# RS-485.net
KiCad netlist of a schematic drawn in Altium Designer
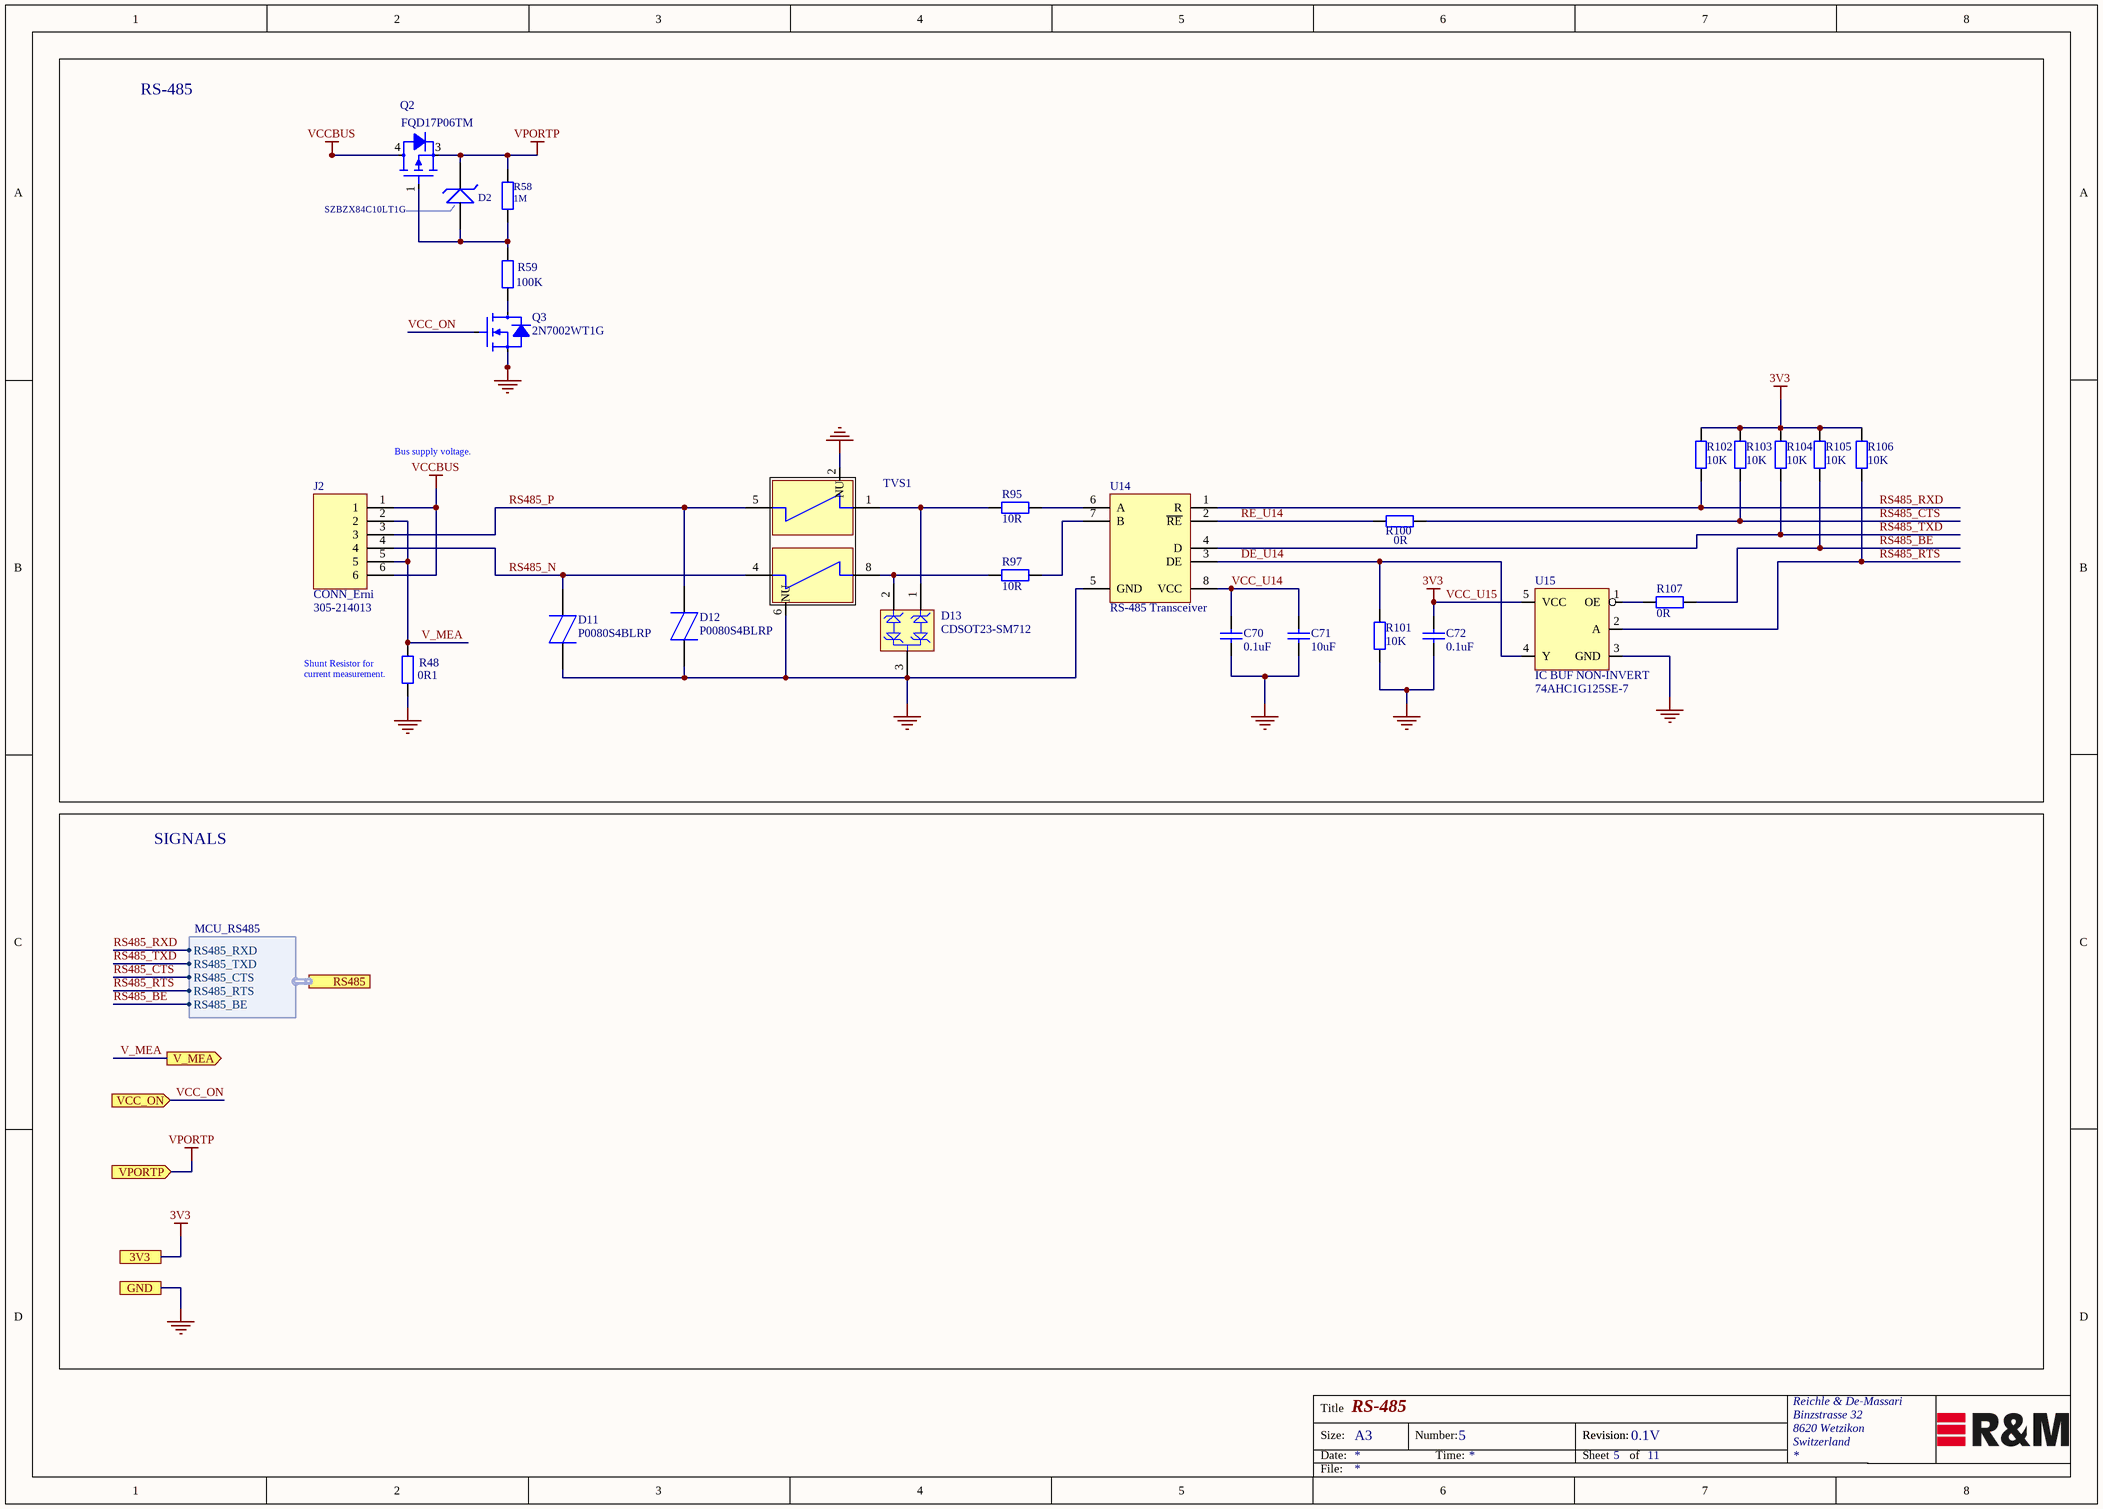
[diagram p0: RS-485.SchDoc]

(export (version "E")
  (design (tool "Eeschema 10.0.6"))
  (components
    (comp (ref "C70")
      (value "0.1uF")
      (footprint "Ceramic Capacitor 0402 EIA")
      (description "0.1µF ±20% 10V Ceramic Capacitor X5R 0402 (1005 Metric)")
      (fields (field (name "TOLERANCE") "20%") (field (name "VOLTAGE") "10VDC"))
      (libsource (lib "RDM_ALT_SCH") (part "Cap_0.1uF_0402_10V"))
    )
    (comp (ref "C71")
      (value "10uF")
      (footprint "Ceramic Capacitor 0402 EIA")
      (description "10µF ±20% 10V Ceramic Capacitor X5R 0402 (1005 Metric)")
      (fields (field (name "TOLERANCE") "20%") (field (name "VOLTAGE") "10VDC"))
      (libsource (lib "RDM_ALT_SCH") (part "Cap_10uF_0402_10V"))
    )
    (comp (ref "C72")
      (value "0.1uF")
      (footprint "Ceramic Capacitor 0402 EIA")
      (description "0.1µF ±20% 10V Ceramic Capacitor X5R 0402 (1005 Metric)")
      (fields (field (name "TOLERANCE") "20%") (field (name "VOLTAGE") "10VDC"))
      (libsource (lib "RDM_ALT_SCH") (part "Cap_0.1uF_0402_10V"))
    )
    (comp (ref "D2")
      (value "SZBZX84C10LT1G")
      (footprint "SOT-23_BZX84")
      (description "Zener Diode 10V 225mW ±6% Oberflächenmontage SOT-23-3 (TO-236)")
      (fields (field (name "MANUFACTURER") "ON Semiconductor") (field (name "POWER") "225mW"))
      (libsource (lib "RDM_ALT_SCH") (part "Diode_SZBZX84C10LT1G"))
    )
    (comp (ref "D11")
      (value "P0080S4BLRP")
      (footprint "P0080S4BLRP")
      (fields (field (name "MANUFACTURER") "Littelfuse") (field (name "MANUFACTURER PARTNR") "P0080S4BLRP"))
      (libsource (lib "RDM_ALT_SCH") (part "P0080S4BLRP"))
    )
    (comp (ref "D12")
      (value "P0080S4BLRP")
      (footprint "P0080S4BLRP")
      (fields (field (name "MANUFACTURER") "Littelfuse") (field (name "MANUFACTURER PARTNR") "P0080S4BLRP"))
      (libsource (lib "RDM_ALT_SCH") (part "P0080S4BLRP"))
    )
    (comp (ref "D13")
      (value "CDSOT23-SM712")
      (footprint "BOUR-SOT23-3_V")
      (description "TVSDiode, 26V, 14V Clamp 17A (8/20µs) Ipp, Surface Mount SOT-23-3, Applications RS-485")
      (fields (field (name "MANUFACTURER") "Bourns") (field (name "VOLTAGE") "26V, 14V"))
      (libsource (lib "RDM_ALT_SCH") (part "Diode_TVS_26V"))
    )
    (comp (ref "J2")
      (value "CONN_Erni")
      (footprint "ERNI_214013 Randmontage_6_R")
      (description "Headers & Wire Housings 6P 1.27MM SNGL ROW R/A MALE BLK")
      (fields (field (name "MANUFACTURER") "ERNI") (field (name "SUPPLIER PART NUMBER 1") "305-214013"))
      (libsource (lib "RDM_ALT_SCH") (part "CONN_Erni_6_214013"))
    )
    (comp (ref "Q2")
      (value "FQD17P06TM")
      (footprint "DPAK_FQU17P06")
      (description "P-Channel 60V 12A (Tc) 2.5W (Ta), 44W (Tc) Surface Mount D-Pak")
      (fields (field (name "TOLERANCE") "NA") (field (name "VOLTAGE") "60V"))
      (libsource (lib "RDM_ALT_SCH") (part "FQD17P06TM"))
    )
    (comp (ref "Q3")
      (value "2N7002WT1G")
      (footprint "SOT323_2N7002WT1G")
      (description "N-Channel 60V 310mA (Ta) 280mW (Tj) Surface Mount SC-70-3 (SOT323)")
      (fields (field (name "TOLERANCE") "NA") (field (name "VOLTAGE") "60V"))
      (libsource (lib "RDM_ALT_SCH") (part "2N7002WT1G"))
    )
    (comp (ref "R48")
      (value "0R1")
      (footprint "Resistor 4527")
      (fields
        (field (name "TOLERANCE") "±1%")
        (field (name "POWER") "5W")
        (field (name "MANUFACTURER") "Vishay / Dale")
      )
      (libsource (lib "RDM_ALT_SCH") (part "Res_0R1"))
    )
    (comp (ref "R58")
      (value "1M")
      (footprint "Resistor 0402 EIA")
      (description "1 MOhms ±1% 0.1W, 1/10W Chip Resistor 0402 (1005 Metric) Anti-Sulfur Thin Film")
      (fields (field (name "MANUFACTURER") "Vishay Beyschlag") (field (name "POWER") "0.1W, 1/10W"))
      (libsource (lib "RDM_ALT_SCH") (part "Res_1M_0402"))
    )
    (comp (ref "R59")
      (value "100K")
      (footprint "Resistor 0402 EIA")
      (description "100 kOhms ±0,1% 0,063W, 1/16W Chip-Widerstand 0402 (1005 metrisch) Dünnschicht")
      (fields (field (name "TOLERANCE") "±0.1%") (field (name "POWER") "0,063W, 1/16W"))
      (libsource (lib "RDM_ALT_SCH") (part "Res_100K_0402"))
    )
    (comp (ref "R95")
      (value "10R")
      (footprint "Resistor 0603 EIA")
      (description "SMD 1/4watt 10ohms 1%")
      (fields (field (name "TOLERANCE") "1%") (field (name "POWER") "250mW"))
      (libsource (lib "RDM_ALT_SCH") (part "Res_10R_0603"))
    )
    (comp (ref "R97")
      (value "10R")
      (footprint "Resistor 0603 EIA")
      (description "SMD 1/4watt 10ohms 1%")
      (fields (field (name "TOLERANCE") "1%") (field (name "POWER") "250mW"))
      (libsource (lib "RDM_ALT_SCH") (part "Res_10R_0603"))
    )
    (comp (ref "R100")
      (value "0R")
      (footprint "Resistor 0402 EIA")
      (description "0 Ohms Resistor 0402")
      (fields (field (name "POWER") "100mW") (field (name "MANUFACTURER") "Panasonic Electronic Components"))
      (libsource (lib "RDM_ALT_SCH") (part "Res_0R_0402"))
    )
    (comp (ref "R101")
      (value "10K")
      (footprint "Resistor 0402 EIA")
      (description "SMD 10K ohm 1% 50V General Purpose")
      (fields (field (name "TOLERANCE") "1%") (field (name "POWER") "63mW"))
      (libsource (lib "RDM_ALT_SCH") (part "Res_10K_0402"))
    )
    (comp (ref "R102")
      (value "10K")
      (footprint "Resistor 0402 EIA")
      (description "SMD 10K ohm 1% 50V General Purpose")
      (fields (field (name "TOLERANCE") "1%") (field (name "POWER") "63mW"))
      (libsource (lib "RDM_ALT_SCH") (part "Res_10K_0402"))
    )
    (comp (ref "R103")
      (value "10K")
      (footprint "Resistor 0402 EIA")
      (description "SMD 10K ohm 1% 50V General Purpose")
      (fields (field (name "TOLERANCE") "1%") (field (name "POWER") "63mW"))
      (libsource (lib "RDM_ALT_SCH") (part "Res_10K_0402"))
    )
    (comp (ref "R104")
      (value "10K")
      (footprint "Resistor 0402 EIA")
      (description "SMD 10K ohm 1% 50V General Purpose")
      (fields (field (name "TOLERANCE") "1%") (field (name "POWER") "63mW"))
      (libsource (lib "RDM_ALT_SCH") (part "Res_10K_0402"))
    )
    (comp (ref "R105")
      (value "10K")
      (footprint "Resistor 0402 EIA")
      (description "SMD 10K ohm 1% 50V General Purpose")
      (fields (field (name "TOLERANCE") "1%") (field (name "POWER") "63mW"))
      (libsource (lib "RDM_ALT_SCH") (part "Res_10K_0402"))
    )
    (comp (ref "R106")
      (value "10K")
      (footprint "Resistor 0402 EIA")
      (description "SMD 10K ohm 1% 50V General Purpose")
      (fields (field (name "TOLERANCE") "1%") (field (name "POWER") "63mW"))
      (libsource (lib "RDM_ALT_SCH") (part "Res_10K_0402"))
    )
    (comp (ref "R107")
      (value "0R")
      (footprint "Resistor 0402 EIA")
      (description "0 Ohms Resistor 0402")
      (fields (field (name "POWER") "100mW") (field (name "MANUFACTURER") "Panasonic Electronic Components"))
      (libsource (lib "RDM_ALT_SCH") (part "Res_0R_0402"))
    )
    (comp (ref "TVS1")
      (value "TBU-CA065-200-WH")
      (footprint "Bourns_TBU_PL060_WH")
      (description "TBU-PL Series dual 50 ohm Surge Suppressors, bi-directional")
      (fields (field (name "MANUFACTURER") "Bourns") (field (name "VOLTAGE") "350V"))
      (libsource (lib "RDM_ALT_SCH") (part "Bourns_TBU-PL060-200-WH"))
    )
    (comp (ref "U14")
      (value "RS-485 Transceiver")
      (footprint "TI_D (R-PDSO-G8)_8_R")
      (description "RS-485 Interface IC 3.3V Differential Transceivers")
      (fields (field (name "MANUFACTURER") "Texas Instruments"))
      (libsource (lib "RDM_ALT_SCH") (part "SN65HVD11DR"))
    )
    (comp (ref "U15")
      (value "IC BUF NON-INVERT")
      (footprint "SOT353")
      (description "Buffer, Non-Inverting 1 Element 1 Bit per Element 3-State Output SOT-353")
      (fields
        (field (name "MANUFACTURER") "Diodes Incorporated")
        (field (name "MANUFACTURER PARTNR") "74AHC1G125SE-7")
      )
      (libsource (lib "RDM_ALT_SCH") (part "74AHC1G125SE-7"))
    )
  )
  (nets
    (net (code "2") (name "/DE_U14") (class "Default")
      (node (ref "R101") (pin "1") (pinfunction "1_1") (pintype "passive"))
      (node (ref "U14") (pin "3") (pinfunction "DE_3") (pintype "passive"))
      (node (ref "U15") (pin "4") (pinfunction "Y_4") (pintype "passive"))
    )
    (net (code "3") (name "/RE_U14") (class "Default")
      (node (ref "R100") (pin "1") (pinfunction "1_1") (pintype "passive"))
      (node (ref "U14") (pin "2") (pinfunction "~{RE}_2") (pintype "passive"))
    )
    (net (code "4") (name "/RS485_BE") (class "Default")
      (node (ref "R105") (pin "2") (pinfunction "2_2") (pintype "passive"))
      (node (ref "R107") (pin "2") (pinfunction "2_2") (pintype "passive"))
    )
    (net (code "5") (name "/RS485_CTS") (class "Default")
      (node (ref "R100") (pin "2") (pinfunction "2_2") (pintype "passive"))
      (node (ref "R103") (pin "2") (pinfunction "2_2") (pintype "passive"))
    )
    (net (code "6") (name "/RS485_N") (class "Default")
      (node (ref "D11") (pin "2") (pinfunction "K_2") (pintype "passive"))
      (node (ref "J2") (pin "4") (pinfunction "4_4") (pintype "passive"))
      (node (ref "TVS1") (pin "4") (pinfunction "4_4") (pintype "passive"))
    )
    (net (code "7") (name "/RS485_P") (class "Default")
      (node (ref "D12") (pin "2") (pinfunction "K_2") (pintype "passive"))
      (node (ref "J2") (pin "3") (pinfunction "3_3") (pintype "passive"))
      (node (ref "TVS1") (pin "5") (pinfunction "5_5") (pintype "passive"))
    )
    (net (code "8") (name "/RS485_RTS") (class "Default")
      (node (ref "R106") (pin "2") (pinfunction "2_2") (pintype "passive"))
      (node (ref "U15") (pin "2") (pinfunction "A_2") (pintype "passive"))
    )
    (net (code "9") (name "/RS485_RXD") (class "Default")
      (node (ref "R102") (pin "2") (pinfunction "2_2") (pintype "passive"))
      (node (ref "U14") (pin "1") (pinfunction "R_1") (pintype "tri_state"))
    )
    (net (code "10") (name "/RS485_TXD") (class "Default")
      (node (ref "R104") (pin "2") (pinfunction "2_2") (pintype "passive"))
      (node (ref "U14") (pin "4") (pinfunction "D_4") (pintype "passive"))
    )
    (net (code "11") (name "/VCC_ON") (class "Default")
      (node (ref "Q3") (pin "1") (pinfunction "1_1") (pintype "passive"))
    )
    (net (code "12") (name "/VCC_U14") (class "Default")
      (node (ref "C70") (pin "2") (pinfunction "2_2") (pintype "passive"))
      (node (ref "C71") (pin "2") (pinfunction "2_2") (pintype "passive"))
      (node (ref "U14") (pin "8") (pinfunction "VCC_8") (pintype "power_in"))
    )
    (net (code "13") (name "/V_MEA") (class "Default")
      (node (ref "J2") (pin "2") (pinfunction "2_2") (pintype "passive"))
      (node (ref "J2") (pin "5") (pinfunction "5_5") (pintype "passive"))
      (node (ref "R48") (pin "1") (pinfunction "1_1") (pintype "passive"))
    )
    (net (code "15") (name "3V3") (class "Default")
      (node (ref "C72") (pin "2") (pinfunction "2_2") (pintype "passive"))
      (node (ref "R102") (pin "1") (pinfunction "1_1") (pintype "passive"))
      (node (ref "R103") (pin "1") (pinfunction "1_1") (pintype "passive"))
      (node (ref "R104") (pin "1") (pinfunction "1_1") (pintype "passive"))
      (node (ref "R105") (pin "1") (pinfunction "1_1") (pintype "passive"))
      (node (ref "R106") (pin "1") (pinfunction "1_1") (pintype "passive"))
      (node (ref "U15") (pin "5") (pinfunction "VCC_5") (pintype "passive"))
    )
    (net (code "16") (name "GND") (class "Default")
      (node (ref "C70") (pin "1") (pinfunction "1_1") (pintype "passive"))
      (node (ref "C71") (pin "1") (pinfunction "1_1") (pintype "passive"))
      (node (ref "C72") (pin "1") (pinfunction "1_1") (pintype "passive"))
      (node (ref "D11") (pin "1") (pinfunction "A_1") (pintype "passive"))
      (node (ref "D12") (pin "1") (pinfunction "A_1") (pintype "passive"))
      (node (ref "D13") (pin "3") (pinfunction "3_3") (pintype "passive"))
      (node (ref "Q3") (pin "2") (pinfunction "2_2") (pintype "passive"))
      (node (ref "R101") (pin "2") (pinfunction "2_2") (pintype "passive"))
      (node (ref "R48") (pin "2") (pinfunction "2_2") (pintype "passive"))
      (node (ref "TVS1") (pin "2") (pinfunction "NU_2") (pintype "passive"))
      (node (ref "TVS1") (pin "6") (pinfunction "NU_6") (pintype "passive"))
      (node (ref "U14") (pin "5") (pinfunction "GND_5") (pintype "passive"))
      (node (ref "U15") (pin "3") (pinfunction "GND_3") (pintype "passive"))
    )
    (net (code "17") (name "Net-(D2-A)") (class "Default")
      (node (ref "D2") (pin "1") (pinfunction "A_1") (pintype "passive"))
      (node (ref "Q2") (pin "1") (pinfunction "1_1") (pintype "passive"))
      (node (ref "R58") (pin "2") (pinfunction "2_2") (pintype "passive"))
      (node (ref "R59") (pin "1") (pinfunction "1_1") (pintype "passive"))
    )
    (net (code "18") (name "Net-(D13-Pad1)") (class "Default")
      (node (ref "D13") (pin "1") (pinfunction "1_1") (pintype "passive"))
      (node (ref "R95") (pin "1") (pinfunction "1_1") (pintype "passive"))
      (node (ref "TVS1") (pin "1") (pinfunction "1_1") (pintype "passive"))
    )
    (net (code "19") (name "Net-(D13-Pad2)") (class "Default")
      (node (ref "D13") (pin "2") (pinfunction "2_2") (pintype "passive"))
      (node (ref "R97") (pin "1") (pinfunction "1_1") (pintype "passive"))
      (node (ref "TVS1") (pin "8") (pintype "passive"))
    )
    (net (code "20") (name "Net-(Q3-Pad3)") (class "Default")
      (node (ref "Q3") (pin "3") (pinfunction "3_3") (pintype "passive"))
      (node (ref "R59") (pin "2") (pinfunction "2_2") (pintype "passive"))
    )
    (net (code "21") (name "Net-(U14-A)") (class "Default")
      (node (ref "R95") (pin "2") (pinfunction "2_2") (pintype "passive"))
      (node (ref "U14") (pin "6") (pinfunction "A_6") (pintype "passive"))
    )
    (net (code "22") (name "Net-(U14-B)") (class "Default")
      (node (ref "R97") (pin "2") (pinfunction "2_2") (pintype "passive"))
      (node (ref "U14") (pin "7") (pinfunction "B_7") (pintype "passive"))
    )
    (net (code "23") (name "Net-(U15-OE)") (class "Default")
      (node (ref "R107") (pin "1") (pinfunction "1_1") (pintype "passive"))
      (node (ref "U15") (pin "1") (pinfunction "OE_1") (pintype "passive"))
    )
    (net (code "24") (name "VCCBUS") (class "Default")
      (node (ref "J2") (pin "1") (pinfunction "1_1") (pintype "passive"))
      (node (ref "J2") (pin "6") (pinfunction "6_6") (pintype "passive"))
      (node (ref "Q2") (pin "4") (pinfunction "4_4") (pintype "passive"))
    )
    (net (code "25") (name "VPORTP") (class "Default")
      (node (ref "D2") (pin "3") (pinfunction "K_3") (pintype "passive"))
      (node (ref "Q2") (pin "3") (pinfunction "3_3") (pintype "passive"))
      (node (ref "R58") (pin "1") (pinfunction "1_1") (pintype "passive"))
    )
  )
)
